# Altimeter.net
KiCad netlist of a schematic drawn in EAGLE
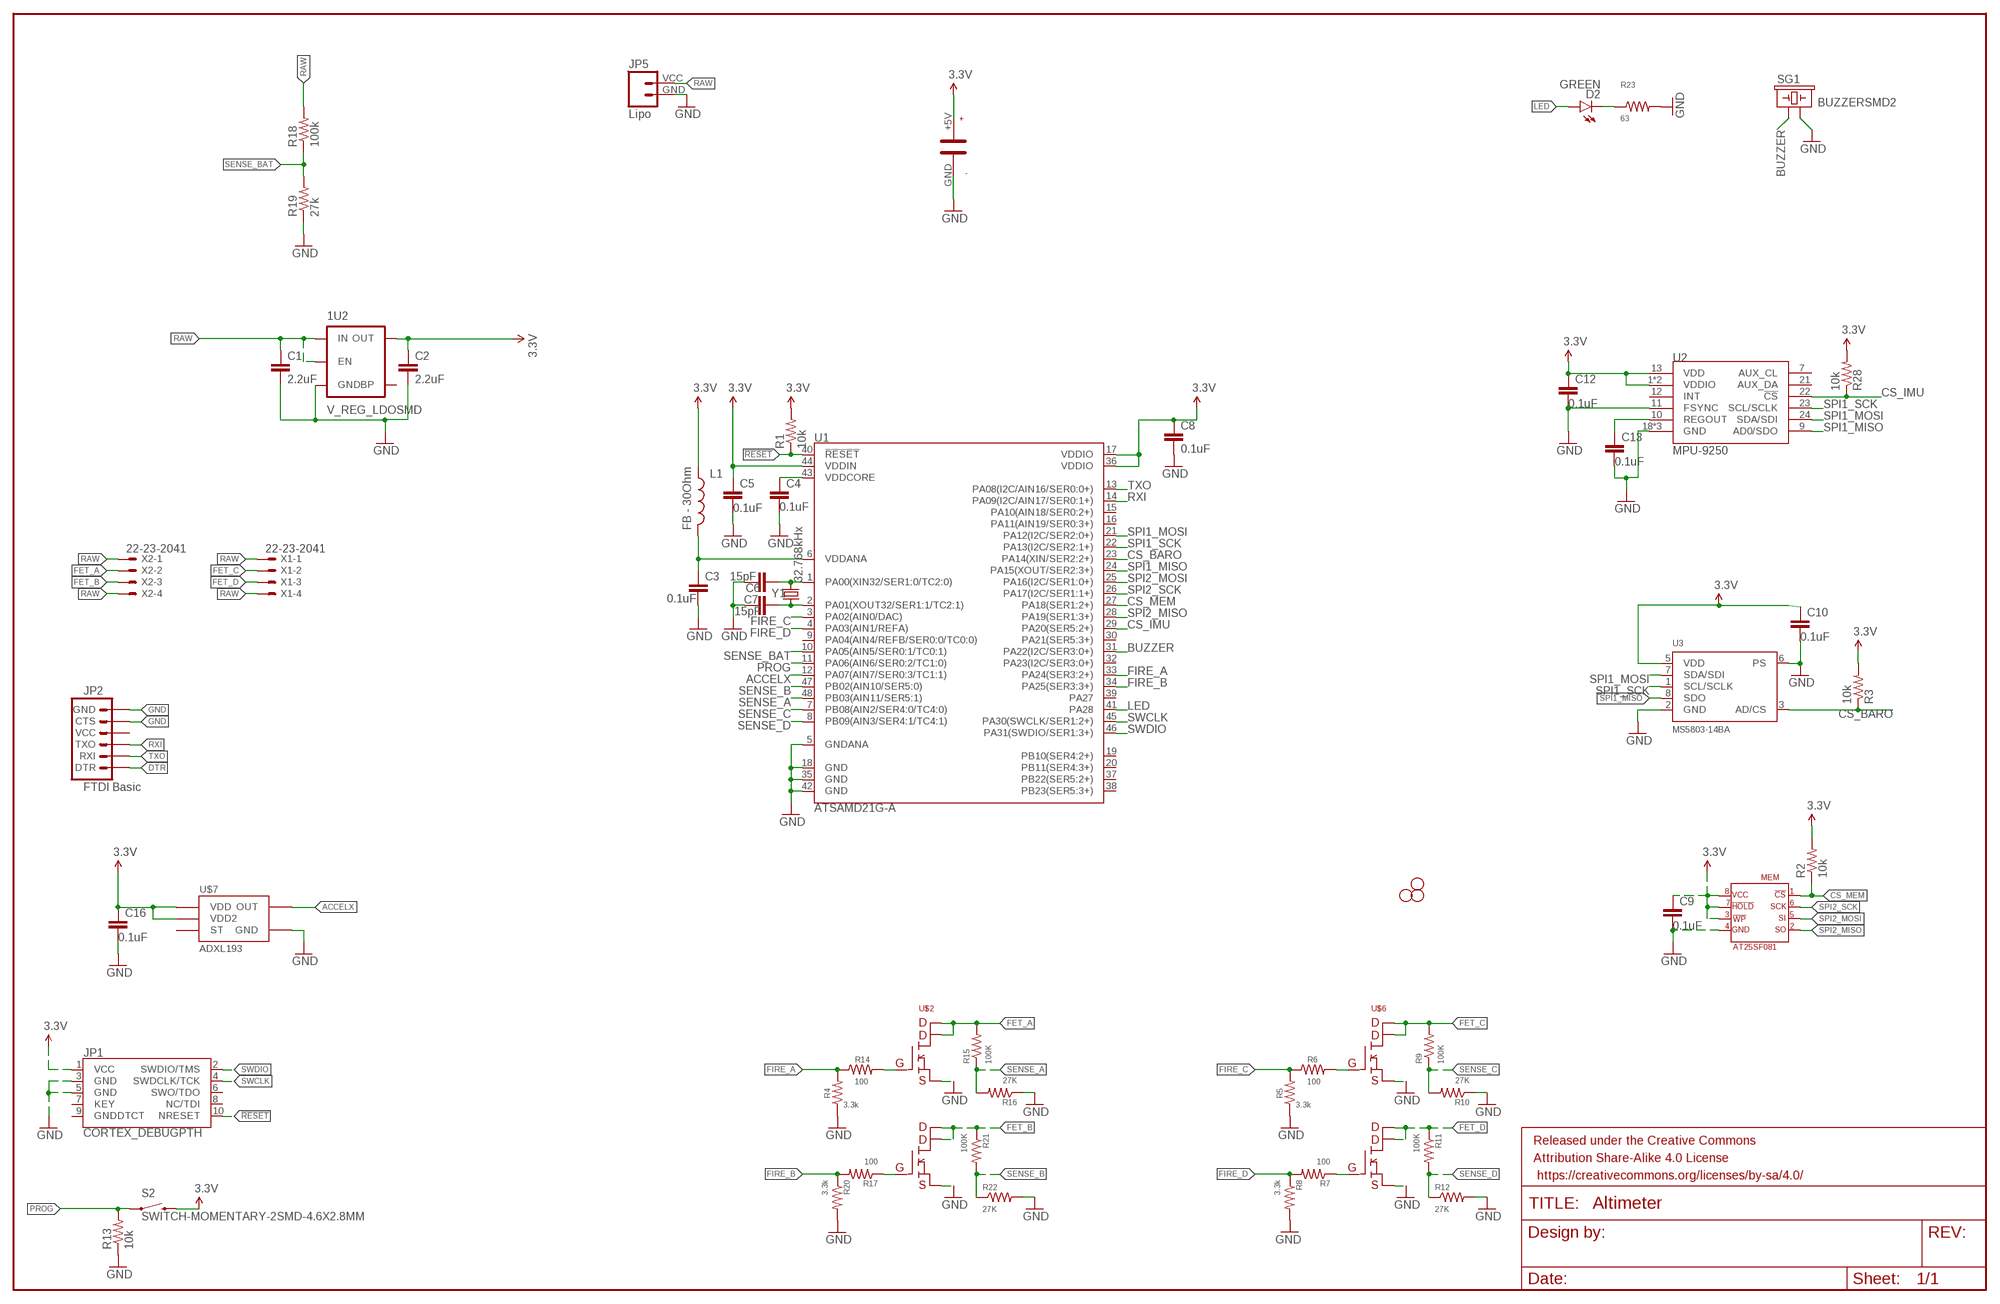
[diagram p0: schematic, sheet 1]

(export (version "E")
  (design (tool "Eeschema 10.0.6"))
  (components
    (comp (ref "1U2")
      (value "V_REG_LDOSMD")
      (footprint "eagle-import:SOT23-5")
      (libsource (lib "eagle-import") (part "V_REG_LDOSMD"))
    )
    (comp (ref "C1")
      (value "2.2uF")
      (footprint "eagle-import:0603-CAP")
      (libsource (lib "eagle-import") (part "CAP0603-CAP"))
    )
    (comp (ref "C2")
      (value "2.2uF")
      (footprint "eagle-import:0603-CAP")
      (libsource (lib "eagle-import") (part "CAP0603-CAP"))
    )
    (comp (ref "C3")
      (value "0.1uF")
      (footprint "eagle-import:0402-CAP")
      (libsource (lib "eagle-import") (part "SparkFun-Passives_CAP0402-CAP"))
    )
    (comp (ref "C4")
      (value "0.1uF")
      (footprint "eagle-import:0402-CAP")
      (libsource (lib "eagle-import") (part "SparkFun-Passives_CAP0402-CAP"))
    )
    (comp (ref "C5")
      (value "0.1uF")
      (footprint "eagle-import:0402-CAP")
      (libsource (lib "eagle-import") (part "SparkFun-Passives_CAP0402-CAP"))
    )
    (comp (ref "C6")
      (value "15pF")
      (footprint "eagle-import:0402-CAP")
      (libsource (lib "eagle-import") (part "SparkFun-Passives_CAP0402-CAP"))
    )
    (comp (ref "C7")
      (value "15pF")
      (footprint "eagle-import:0402-CAP")
      (libsource (lib "eagle-import") (part "SparkFun-Passives_CAP0402-CAP"))
    )
    (comp (ref "C8")
      (value "0.1uF")
      (footprint "eagle-import:0402-CAP")
      (libsource (lib "eagle-import") (part "SparkFun-Passives_CAP0402-CAP"))
    )
    (comp (ref "C9")
      (value "0.1uF")
      (footprint "eagle-import:0402-CAP")
      (libsource (lib "eagle-import") (part "SparkFun-Passives_CAP0402-CAP"))
    )
    (comp (ref "C10")
      (value "0.1uF")
      (footprint "eagle-import:0402-CAP")
      (libsource (lib "eagle-import") (part "SparkFun-Passives_CAP0402-CAP"))
    )
    (comp (ref "C12")
      (value "0.1uF")
      (footprint "eagle-import:0402-CAP")
      (libsource (lib "eagle-import") (part "SparkFun-Passives_CAP0402-CAP"))
    )
    (comp (ref "C13")
      (value "0.1uF")
      (footprint "eagle-import:0402-CAP")
      (libsource (lib "eagle-import") (part "SparkFun-Passives_CAP0402-CAP"))
    )
    (comp (ref "C16")
      (value "0.1uF")
      (footprint "eagle-import:0402-CAP")
      (libsource (lib "eagle-import") (part "SparkFun-Passives_CAP0402-CAP"))
    )
    (comp (ref "D2")
      (value "GREEN")
      (footprint "eagle-import:LED-1206")
      (libsource (lib "eagle-import") (part "LED-GREEN1206"))
    )
    (comp (ref "FRAME1")
      (value "FRAME-LEDGER")
      (footprint "eagle-import:CREATIVE_COMMONS")
      (libsource (lib "eagle-import") (part "FRAME-LEDGER"))
    )
    (comp (ref "JP1")
      (value "CORTEX_DEBUGPTH")
      (footprint "eagle-import:2X5-PTH-1.27MM")
      (libsource (lib "eagle-import") (part "CORTEX_DEBUGPTH"))
    )
    (comp (ref "JP2")
      (value "FTDI Basic")
      (footprint "eagle-import:1X06")
      (libsource (lib "eagle-import") (part "ARDUINO_SERIAL_PROGRAMPTH"))
    )
    (comp (ref "JP5")
      (value "Lipo")
      (footprint "eagle-import:JST-2-SMD-VERT")
      (libsource (lib "eagle-import") (part "M024UCON-15767"))
    )
    (comp (ref "L1")
      (value "FB - 30Ohm")
      (footprint "eagle-import:0603")
      (libsource (lib "eagle-import") (part "INDUCTOR0603"))
    )
    (comp (ref "MEM")
      (value "AT25SF081")
      (footprint "eagle-import:AT25SF081")
      (libsource (lib "eagle-import") (part "AT25SF081"))
    )
    (comp (ref "R1")
      (value "10k")
      (footprint "eagle-import:0402-RES")
      (libsource (lib "eagle-import") (part "RESISTOR0402-RES"))
    )
    (comp (ref "R2")
      (value "10k")
      (footprint "eagle-import:0402-RES")
      (libsource (lib "eagle-import") (part "RESISTOR0402-RES"))
    )
    (comp (ref "R3")
      (value "10k")
      (footprint "eagle-import:0402-RES")
      (libsource (lib "eagle-import") (part "RESISTOR0402-RES"))
    )
    (comp (ref "R4")
      (value "3.3k")
      (footprint "eagle-import:0402-RES")
      (libsource (lib "eagle-import") (part "RESISTOR0402"))
    )
    (comp (ref "R5")
      (value "3.3k")
      (footprint "eagle-import:0402-RES")
      (libsource (lib "eagle-import") (part "RESISTOR0402"))
    )
    (comp (ref "R6")
      (value "100")
      (footprint "eagle-import:0402-RES")
      (libsource (lib "eagle-import") (part "RESISTOR0402"))
    )
    (comp (ref "R7")
      (value "100")
      (footprint "eagle-import:0402-RES")
      (libsource (lib "eagle-import") (part "RESISTOR0402"))
    )
    (comp (ref "R8")
      (value "3.3k")
      (footprint "eagle-import:0402-RES")
      (libsource (lib "eagle-import") (part "RESISTOR0402"))
    )
    (comp (ref "R9")
      (value "100K")
      (footprint "eagle-import:0402-RES")
      (libsource (lib "eagle-import") (part "RESISTOR0402"))
    )
    (comp (ref "R10")
      (value "27K")
      (footprint "eagle-import:0402-RES")
      (libsource (lib "eagle-import") (part "RESISTOR0402"))
    )
    (comp (ref "R11")
      (value "100K")
      (footprint "eagle-import:0402-RES")
      (libsource (lib "eagle-import") (part "RESISTOR0402"))
    )
    (comp (ref "R12")
      (value "27K")
      (footprint "eagle-import:0402-RES")
      (libsource (lib "eagle-import") (part "RESISTOR0402"))
    )
    (comp (ref "R13")
      (value "10k")
      (footprint "eagle-import:0402-RES")
      (libsource (lib "eagle-import") (part "RESISTOR0402-RES"))
    )
    (comp (ref "R14")
      (value "100")
      (footprint "eagle-import:0402-RES")
      (libsource (lib "eagle-import") (part "RESISTOR0402"))
    )
    (comp (ref "R15")
      (value "100K")
      (footprint "eagle-import:0402-RES")
      (libsource (lib "eagle-import") (part "RESISTOR0402"))
    )
    (comp (ref "R16")
      (value "27K")
      (footprint "eagle-import:0402-RES")
      (libsource (lib "eagle-import") (part "RESISTOR0402"))
    )
    (comp (ref "R17")
      (value "100")
      (footprint "eagle-import:0402-RES")
      (libsource (lib "eagle-import") (part "RESISTOR0402"))
    )
    (comp (ref "R18")
      (value "100k")
      (footprint "eagle-import:0402-RES")
      (libsource (lib "eagle-import") (part "RESISTOR0402-RES"))
    )
    (comp (ref "R19")
      (value "27k")
      (footprint "eagle-import:0402-RES")
      (libsource (lib "eagle-import") (part "RESISTOR0402-RES"))
    )
    (comp (ref "R20")
      (value "3.3k")
      (footprint "eagle-import:0402-RES")
      (libsource (lib "eagle-import") (part "RESISTOR0402"))
    )
    (comp (ref "R21")
      (value "100K")
      (footprint "eagle-import:0402-RES")
      (libsource (lib "eagle-import") (part "RESISTOR0402"))
    )
    (comp (ref "R22")
      (value "27K")
      (footprint "eagle-import:0402-RES")
      (libsource (lib "eagle-import") (part "RESISTOR0402"))
    )
    (comp (ref "R23")
      (value "63")
      (footprint "eagle-import:0402-RES")
      (libsource (lib "eagle-import") (part "RESISTOR0402"))
    )
    (comp (ref "R28")
      (value "10k")
      (footprint "eagle-import:0402-RES")
      (libsource (lib "eagle-import") (part "RESISTOR0402-RES"))
    )
    (comp (ref "S2")
      (value "SWITCH-MOMENTARY-2SMD-4.6X2.8MM")
      (footprint "eagle-import:TACTILE_SWITCH_SMD_4.6X2.8MM")
      (libsource (lib "eagle-import") (part "SWITCH-MOMENTARY-2SMD-4.6X2.8MM"))
    )
    (comp (ref "SG1")
      (value "BUZZERSMD2")
      (footprint "eagle-import:BUZZER-CCV")
      (libsource (lib "eagle-import") (part "BUZZERSMD2"))
    )
    (comp (ref "STANDOFF2")
      (value "STAND-OFF")
      (footprint "eagle-import:STAND-OFF")
      (libsource (lib "eagle-import") (part "STAND-OFF"))
    )
    (comp (ref "STANDOFF3")
      (value "STAND-OFF")
      (footprint "eagle-import:STAND-OFF")
      (libsource (lib "eagle-import") (part "STAND-OFF"))
    )
    (comp (ref "STANDOFF4")
      (value "STAND-OFF")
      (footprint "eagle-import:STAND-OFF")
      (libsource (lib "eagle-import") (part "STAND-OFF"))
    )
    (comp (ref "U$1")
      (value "PB-5R0H104-R")
      (footprint "eagle-import:PB-5R0H104-R")
      (libsource (lib "eagle-import") (part "PB-5R0H104-R"))
    )
    (comp (ref "U$2")
      (value "SI7232DN")
      (footprint "eagle-import:SI7232DN")
      (libsource (lib "eagle-import") (part "SI7232DN"))
    )
    (comp (ref "U$6")
      (value "SI7232DN")
      (footprint "eagle-import:SI7232DN")
      (libsource (lib "eagle-import") (part "SI7232DN"))
    )
    (comp (ref "U$7")
      (value "ADXL193")
      (footprint "eagle-import:ADXL193")
      (libsource (lib "eagle-import") (part "ADXL193"))
    )
    (comp (ref "U1")
      (value "ATSAMD21G-A")
      (footprint "eagle-import:TQFP-48")
      (libsource (lib "eagle-import") (part "ATSAMD21G-A"))
    )
    (comp (ref "U2")
      (value "MPU-9250")
      (footprint "eagle-import:QFN24_PAD")
      (libsource (lib "eagle-import") (part "MPU-9250"))
    )
    (comp (ref "U3")
      (value "MS5803-14BA")
      (footprint "eagle-import:MS5803")
      (libsource (lib "eagle-import") (part "MS5803-14BA"))
    )
    (comp (ref "X1")
      (value "22-23-2041")
      (footprint "eagle-import:22-23-2041")
      (fields (field (name "MF") "MOLEX"))
      (libsource (lib "eagle-import") (part "22-23-2041"))
    )
    (comp (ref "X2")
      (value "22-23-2041")
      (footprint "eagle-import:22-23-2041")
      (fields (field (name "MF") "MOLEX"))
      (libsource (lib "eagle-import") (part "22-23-2041"))
    )
    (comp (ref "Y1")
      (value "32.768kHx")
      (footprint "eagle-import:CRYSTAL-SMD-3.2X1.5MM")
      (libsource (lib "eagle-import") (part "CRYSTAL3.2X1.5MM"))
    )
  )
  (nets
    (net (code "1") (name "/BUZZER") (class "Default")
      (node (ref "SG1") (pin "+") (pinfunction "1_+") (pintype "passive"))
      (node (ref "U1") (pin "31") (pinfunction "PA22(I2C/SER3:0+)_31") (pintype "bidirectional"))
    )
    (net (code "2") (name "/CS_BARO") (class "Default")
      (node (ref "R3") (pin "1") (pinfunction "1_1") (pintype "passive"))
      (node (ref "U1") (pin "23") (pinfunction "PA14(XIN/SER2:2+)_23") (pintype "bidirectional"))
      (node (ref "U3") (pin "3") (pinfunction "AD/CS_3") (pintype "bidirectional"))
    )
    (net (code "3") (name "/CS_IMU") (class "Default")
      (node (ref "R28") (pin "1") (pinfunction "1_1") (pintype "passive"))
      (node (ref "U1") (pin "29") (pinfunction "PA20(SER5:2+)_29") (pintype "bidirectional"))
      (node (ref "U2") (pin "22") (pinfunction "~{CS}_22") (pintype "bidirectional"))
    )
    (net (code "4") (name "/SPI1_MOSI") (class "Default")
      (node (ref "U1") (pin "21") (pinfunction "PA12(I2C/SER2:0+)_21") (pintype "bidirectional"))
      (node (ref "U2") (pin "24") (pinfunction "SDA/SDI_24") (pintype "bidirectional"))
      (node (ref "U3") (pin "7") (pinfunction "SDA/SDI_7") (pintype "bidirectional"))
    )
    (net (code "5") (name "/SPI1_SCK") (class "Default")
      (node (ref "U1") (pin "22") (pinfunction "PA13(I2C/SER2:1+)_22") (pintype "bidirectional"))
      (node (ref "U2") (pin "23") (pinfunction "SCL/SCLK_23") (pintype "bidirectional"))
      (node (ref "U3") (pin "1") (pinfunction "SCL/SCLK_1") (pintype "bidirectional"))
    )
    (net (code "6") (name "/~{RESET}") (class "Default")
      (node (ref "JP1") (pin "10") (pinfunction "NRESET_10") (pintype "bidirectional"))
      (node (ref "R1") (pin "1") (pinfunction "1_1") (pintype "passive"))
      (node (ref "U1") (pin "40") (pinfunction "~{RESET}_40") (pintype "bidirectional"))
    )
    (net (code "7") (name "3.3V") (class "Default")
      (node (ref "1U2") (pin "5") (pinfunction "OUT_5") (pintype "passive"))
      (node (ref "C10") (pin "1") (pinfunction "1_1") (pintype "passive"))
      (node (ref "C12") (pin "1") (pinfunction "1_1") (pintype "passive"))
      (node (ref "C16") (pin "1") (pinfunction "1_1") (pintype "passive"))
      (node (ref "C2") (pin "1") (pinfunction "1_1") (pintype "passive"))
      (node (ref "C5") (pin "1") (pinfunction "1_1") (pintype "passive"))
      (node (ref "C8") (pin "1") (pinfunction "1_1") (pintype "passive"))
      (node (ref "C9") (pin "1") (pinfunction "1_1") (pintype "passive"))
      (node (ref "JP1") (pin "1") (pinfunction "VCC_1") (pintype "bidirectional"))
      (node (ref "L1") (pin "1") (pinfunction "1_1") (pintype "passive"))
      (node (ref "MEM") (pin "!HOLD") (pinfunction "~{HOLD}_!HOLD") (pintype "bidirectional"))
      (node (ref "MEM") (pin "!WP") (pinfunction "~{WP}_!WP") (pintype "bidirectional"))
      (node (ref "MEM") (pin "VCC") (pinfunction "VCC_VCC") (pintype "bidirectional"))
      (node (ref "R1") (pin "2") (pinfunction "2_2") (pintype "passive"))
      (node (ref "R2") (pin "2") (pinfunction "2_2") (pintype "passive"))
      (node (ref "R28") (pin "2") (pinfunction "2_2") (pintype "passive"))
      (node (ref "R3") (pin "2") (pinfunction "2_2") (pintype "passive"))
      (node (ref "S2") (pin "3") (pinfunction "2_3") (pintype "passive"))
      (node (ref "S2") (pin "4") (pinfunction "2_4") (pintype "passive"))
      (node (ref "U$1") (pin "+5V") (pinfunction "+5V_+5V") (pintype "bidirectional"))
      (node (ref "U$7") (pin "P$7") (pinfunction "VDD_P$7") (pintype "bidirectional"))
      (node (ref "U$7") (pin "P$8") (pinfunction "VDD2_P$8") (pintype "bidirectional"))
      (node (ref "U1") (pin "17") (pinfunction "VDDIO_17") (pintype "bidirectional"))
      (node (ref "U1") (pin "36") (pinfunction "VDDIO_36") (pintype "bidirectional"))
      (node (ref "U1") (pin "44") (pinfunction "VDDIN_44") (pintype "bidirectional"))
      (node (ref "U2") (pin "1") (pinfunction "VDDIO_1") (pintype "bidirectional"))
      (node (ref "U2") (pin "13") (pinfunction "VDD_13") (pintype "bidirectional"))
      (node (ref "U2") (pin "8") (pinfunction "VDDIO_8") (pintype "bidirectional"))
      (node (ref "U3") (pin "5") (pinfunction "VDD_5") (pintype "bidirectional"))
    )
    (net (code "8") (name "ACCELX") (class "Default")
      (node (ref "U$7") (pin "P$6") (pinfunction "OUT_P$6") (pintype "bidirectional"))
      (node (ref "U1") (pin "12") (pinfunction "PA07(AIN7/SER0:3/TC1:1)_12") (pintype "bidirectional"))
    )
    (net (code "9") (name "CS_MEM") (class "Default")
      (node (ref "MEM") (pin "!CS") (pinfunction "~{CS}_!CS") (pintype "bidirectional"))
      (node (ref "R2") (pin "1") (pinfunction "1_1") (pintype "passive"))
      (node (ref "U1") (pin "27") (pinfunction "PA18(SER1:2+)_27") (pintype "bidirectional"))
    )
    (net (code "10") (name "DTR") (class "Default")
      (node (ref "JP2") (pin "1") (pinfunction "DTR_1") (pintype "passive"))
    )
    (net (code "11") (name "FET_A") (class "Default")
      (node (ref "R15") (pin "2") (pinfunction "2_2") (pintype "passive"))
      (node (ref "U$2") (pin "7") (pinfunction "PIN7_7") (pintype "bidirectional"))
      (node (ref "U$2") (pin "8") (pinfunction "PIN8_8") (pintype "bidirectional"))
      (node (ref "X2") (pin "2") (pinfunction "S_2") (pintype "passive"))
    )
    (net (code "12") (name "FET_B") (class "Default")
      (node (ref "R21") (pin "1") (pinfunction "1_1") (pintype "passive"))
      (node (ref "U$2") (pin "5") (pinfunction "PIN5_5") (pintype "bidirectional"))
      (node (ref "U$2") (pin "6") (pinfunction "PIN6_6") (pintype "bidirectional"))
      (node (ref "X2") (pin "3") (pinfunction "S_3") (pintype "passive"))
    )
    (net (code "13") (name "FET_C") (class "Default")
      (node (ref "R9") (pin "2") (pinfunction "2_2") (pintype "passive"))
      (node (ref "U$6") (pin "7") (pinfunction "PIN7_7") (pintype "bidirectional"))
      (node (ref "U$6") (pin "8") (pinfunction "PIN8_8") (pintype "bidirectional"))
      (node (ref "X1") (pin "2") (pinfunction "S_2") (pintype "passive"))
    )
    (net (code "14") (name "FET_D") (class "Default")
      (node (ref "R11") (pin "1") (pinfunction "1_1") (pintype "passive"))
      (node (ref "U$6") (pin "5") (pinfunction "PIN5_5") (pintype "bidirectional"))
      (node (ref "U$6") (pin "6") (pinfunction "PIN6_6") (pintype "bidirectional"))
      (node (ref "X1") (pin "3") (pinfunction "S_3") (pintype "passive"))
    )
    (net (code "15") (name "FIRE_A") (class "Default")
      (node (ref "R14") (pin "1") (pinfunction "1_1") (pintype "passive"))
      (node (ref "R4") (pin "2") (pinfunction "2_2") (pintype "passive"))
      (node (ref "U1") (pin "33") (pinfunction "PA24(SER3:2+)_33") (pintype "bidirectional"))
    )
    (net (code "16") (name "FIRE_B") (class "Default")
      (node (ref "R17") (pin "2") (pinfunction "2_2") (pintype "passive"))
      (node (ref "R20") (pin "1") (pinfunction "1_1") (pintype "passive"))
      (node (ref "U1") (pin "34") (pinfunction "PA25(SER3:3+)_34") (pintype "bidirectional"))
    )
    (net (code "17") (name "FIRE_C") (class "Default")
      (node (ref "R5") (pin "2") (pinfunction "2_2") (pintype "passive"))
      (node (ref "R6") (pin "1") (pinfunction "1_1") (pintype "passive"))
      (node (ref "U1") (pin "3") (pinfunction "PA02(AIN0/DAC)_3") (pintype "bidirectional"))
    )
    (net (code "18") (name "FIRE_D") (class "Default")
      (node (ref "R7") (pin "2") (pinfunction "2_2") (pintype "passive"))
      (node (ref "R8") (pin "1") (pinfunction "1_1") (pintype "passive"))
      (node (ref "U1") (pin "4") (pinfunction "PA03(AIN1/REFA)_4") (pintype "bidirectional"))
    )
    (net (code "19") (name "GND") (class "Default")
      (node (ref "1U2") (pin "2") (pinfunction "GND_2") (pintype "input"))
      (node (ref "C1") (pin "2") (pinfunction "2_2") (pintype "passive"))
      (node (ref "C10") (pin "2") (pinfunction "2_2") (pintype "passive"))
      (node (ref "C12") (pin "2") (pinfunction "2_2") (pintype "passive"))
      (node (ref "C13") (pin "2") (pinfunction "2_2") (pintype "passive"))
      (node (ref "C16") (pin "2") (pinfunction "2_2") (pintype "passive"))
      (node (ref "C2") (pin "2") (pinfunction "2_2") (pintype "passive"))
      (node (ref "C3") (pin "2") (pinfunction "2_2") (pintype "passive"))
      (node (ref "C4") (pin "2") (pinfunction "2_2") (pintype "passive"))
      (node (ref "C5") (pin "2") (pinfunction "2_2") (pintype "passive"))
      (node (ref "C6") (pin "2") (pinfunction "2_2") (pintype "passive"))
      (node (ref "C7") (pin "2") (pinfunction "2_2") (pintype "passive"))
      (node (ref "C8") (pin "2") (pinfunction "2_2") (pintype "passive"))
      (node (ref "C9") (pin "2") (pinfunction "2_2") (pintype "passive"))
      (node (ref "JP1") (pin "3") (pinfunction "GND_3") (pintype "bidirectional"))
      (node (ref "JP1") (pin "5") (pinfunction "GND_5") (pintype "bidirectional"))
      (node (ref "JP2") (pin "5") (pinfunction "CTS_5") (pintype "passive"))
      (node (ref "JP2") (pin "6") (pinfunction "GND_6") (pintype "passive"))
      (node (ref "JP5") (pin "GND") (pinfunction "1_GND") (pintype "passive"))
      (node (ref "MEM") (pin "GND") (pinfunction "GND_GND") (pintype "bidirectional"))
      (node (ref "R10") (pin "1") (pinfunction "1_1") (pintype "passive"))
      (node (ref "R12") (pin "2") (pinfunction "2_2") (pintype "passive"))
      (node (ref "R13") (pin "1") (pinfunction "1_1") (pintype "passive"))
      (node (ref "R16") (pin "1") (pinfunction "1_1") (pintype "passive"))
      (node (ref "R19") (pin "1") (pinfunction "1_1") (pintype "passive"))
      (node (ref "R20") (pin "2") (pinfunction "2_2") (pintype "passive"))
      (node (ref "R22") (pin "2") (pinfunction "2_2") (pintype "passive"))
      (node (ref "R23") (pin "2") (pinfunction "2_2") (pintype "passive"))
      (node (ref "R4") (pin "1") (pinfunction "1_1") (pintype "passive"))
      (node (ref "R5") (pin "1") (pinfunction "1_1") (pintype "passive"))
      (node (ref "R8") (pin "2") (pinfunction "2_2") (pintype "passive"))
      (node (ref "SG1") (pin "-") (pinfunction "2_-") (pintype "passive"))
      (node (ref "U$1") (pin "GND") (pinfunction "GND_GND") (pintype "bidirectional"))
      (node (ref "U$2") (pin "1") (pinfunction "PIN1_1") (pintype "bidirectional"))
      (node (ref "U$2") (pin "3") (pinfunction "PIN3_3") (pintype "bidirectional"))
      (node (ref "U$6") (pin "1") (pinfunction "PIN1_1") (pintype "bidirectional"))
      (node (ref "U$6") (pin "3") (pinfunction "PIN3_3") (pintype "bidirectional"))
      (node (ref "U$7") (pin "P$3") (pinfunction "GND_P$3") (pintype "bidirectional"))
      (node (ref "U1") (pin "18") (pinfunction "GND_18") (pintype "bidirectional"))
      (node (ref "U1") (pin "35") (pinfunction "GND_35") (pintype "bidirectional"))
      (node (ref "U1") (pin "42") (pinfunction "GND_42") (pintype "bidirectional"))
      (node (ref "U1") (pin "5") (pinfunction "GNDANA_5") (pintype "bidirectional"))
      (node (ref "U2") (pin "11") (pinfunction "FSYNC_11") (pintype "bidirectional"))
      (node (ref "U2") (pin "18") (pinfunction "GND_18") (pintype "bidirectional"))
      (node (ref "U2") (pin "20") (pinfunction "GND_20") (pintype "bidirectional"))
      (node (ref "U2") (pin "CENTER") (pinfunction "GND_CENTER") (pintype "bidirectional"))
      (node (ref "U3") (pin "2") (pinfunction "GND_2") (pintype "bidirectional"))
      (node (ref "U3") (pin "6") (pinfunction "PS_6") (pintype "bidirectional"))
    )
    (net (code "20") (name "LED") (class "Default")
      (node (ref "D2") (pin "A") (pinfunction "A_A") (pintype "passive"))
      (node (ref "U1") (pin "41") (pinfunction "PA28_41") (pintype "bidirectional"))
    )
    (net (code "21") (name "Net-(D2-PadC)") (class "Default")
      (node (ref "D2") (pin "C") (pinfunction "C_C") (pintype "passive"))
      (node (ref "R23") (pin "1") (pinfunction "1_1") (pintype "passive"))
    )
    (net (code "22") (name "Net-(U$2-PIN2)") (class "Default")
      (node (ref "R14") (pin "2") (pinfunction "2_2") (pintype "passive"))
      (node (ref "U$2") (pin "2") (pinfunction "PIN2_2") (pintype "bidirectional"))
    )
    (net (code "23") (name "Net-(U$2-PIN4)") (class "Default")
      (node (ref "R17") (pin "1") (pinfunction "1_1") (pintype "passive"))
      (node (ref "U$2") (pin "4") (pinfunction "PIN4_4") (pintype "bidirectional"))
    )
    (net (code "24") (name "Net-(U$6-PIN2)") (class "Default")
      (node (ref "R6") (pin "2") (pinfunction "2_2") (pintype "passive"))
      (node (ref "U$6") (pin "2") (pinfunction "PIN2_2") (pintype "bidirectional"))
    )
    (net (code "25") (name "Net-(U$6-PIN4)") (class "Default")
      (node (ref "R7") (pin "1") (pinfunction "1_1") (pintype "passive"))
      (node (ref "U$6") (pin "4") (pinfunction "PIN4_4") (pintype "bidirectional"))
    )
    (net (code "26") (name "Net-(U1-PA00(XIN32{slash}SER1:0{slash}TC2:0))") (class "Default")
      (node (ref "C6") (pin "1") (pinfunction "1_1") (pintype "passive"))
      (node (ref "U1") (pin "1") (pinfunction "PA00(XIN32/SER1:0/TC2:0)_1") (pintype "bidirectional"))
      (node (ref "Y1") (pin "P$2") (pinfunction "2_P$2") (pintype "passive"))
    )
    (net (code "27") (name "Net-(U1-PA01(XOUT32{slash}SER1:1{slash}TC2:1))") (class "Default")
      (node (ref "C7") (pin "1") (pinfunction "1_1") (pintype "passive"))
      (node (ref "U1") (pin "2") (pinfunction "PA01(XOUT32/SER1:1/TC2:1)_2") (pintype "bidirectional"))
      (node (ref "Y1") (pin "P$1") (pinfunction "1_P$1") (pintype "passive"))
    )
    (net (code "28") (name "Net-(U1-VDDANA)") (class "Default")
      (node (ref "C3") (pin "1") (pinfunction "1_1") (pintype "passive"))
      (node (ref "L1") (pin "2") (pinfunction "2_2") (pintype "passive"))
      (node (ref "U1") (pin "6") (pinfunction "VDDANA_6") (pintype "bidirectional"))
    )
    (net (code "29") (name "Net-(U1-VDDCORE)") (class "Default")
      (node (ref "C4") (pin "1") (pinfunction "1_1") (pintype "passive"))
      (node (ref "U1") (pin "43") (pinfunction "VDDCORE_43") (pintype "bidirectional"))
    )
    (net (code "30") (name "Net-(U2-REGOUT)") (class "Default")
      (node (ref "C13") (pin "1") (pinfunction "1_1") (pintype "passive"))
      (node (ref "U2") (pin "10") (pinfunction "REGOUT_10") (pintype "bidirectional"))
    )
    (net (code "31") (name "PROG") (class "Default")
      (node (ref "R13") (pin "2") (pinfunction "2_2") (pintype "passive"))
      (node (ref "S2") (pin "1") (pinfunction "1_1") (pintype "passive"))
      (node (ref "S2") (pin "2") (pinfunction "1_2") (pintype "passive"))
      (node (ref "U1") (pin "11") (pinfunction "PA06(AIN6/SER0:2/TC1:0)_11") (pintype "bidirectional"))
    )
    (net (code "32") (name "RAW") (class "Default")
      (node (ref "1U2") (pin "1") (pinfunction "IN_1") (pintype "input"))
      (node (ref "1U2") (pin "3") (pinfunction "EN_3") (pintype "input"))
      (node (ref "C1") (pin "1") (pinfunction "1_1") (pintype "passive"))
      (node (ref "JP5") (pin "VCC") (pinfunction "2_VCC") (pintype "passive"))
      (node (ref "R18") (pin "2") (pinfunction "2_2") (pintype "passive"))
      (node (ref "X1") (pin "1") (pinfunction "S_1") (pintype "passive"))
      (node (ref "X1") (pin "4") (pinfunction "S_4") (pintype "passive"))
      (node (ref "X2") (pin "1") (pinfunction "S_1") (pintype "passive"))
      (node (ref "X2") (pin "4") (pinfunction "S_4") (pintype "passive"))
    )
    (net (code "33") (name "RXI") (class "Default")
      (node (ref "JP2") (pin "3") (pinfunction "TXO_3") (pintype "passive"))
      (node (ref "U1") (pin "14") (pinfunction "PA09(I2C/AIN17/SER0:1+)_14") (pintype "bidirectional"))
    )
    (net (code "34") (name "SENSE_A") (class "Default")
      (node (ref "R15") (pin "1") (pinfunction "1_1") (pintype "passive"))
      (node (ref "R16") (pin "2") (pinfunction "2_2") (pintype "passive"))
      (node (ref "U1") (pin "48") (pinfunction "PB03(AIN11/SER5:1)_48") (pintype "bidirectional"))
    )
    (net (code "35") (name "SENSE_B") (class "Default")
      (node (ref "R21") (pin "2") (pinfunction "2_2") (pintype "passive"))
      (node (ref "R22") (pin "1") (pinfunction "1_1") (pintype "passive"))
      (node (ref "U1") (pin "47") (pinfunction "PB02(AIN10/SER5:0)_47") (pintype "bidirectional"))
    )
    (net (code "36") (name "SENSE_BAT") (class "Default")
      (node (ref "R18") (pin "1") (pinfunction "1_1") (pintype "passive"))
      (node (ref "R19") (pin "2") (pinfunction "2_2") (pintype "passive"))
      (node (ref "U1") (pin "10") (pinfunction "PA05(AIN5/SER0:1/TC0:1)_10") (pintype "bidirectional"))
    )
    (net (code "37") (name "SENSE_C") (class "Default")
      (node (ref "R10") (pin "2") (pinfunction "2_2") (pintype "passive"))
      (node (ref "R9") (pin "1") (pinfunction "1_1") (pintype "passive"))
      (node (ref "U1") (pin "7") (pinfunction "PB08(AIN2/SER4:0/TC4:0)_7") (pintype "bidirectional"))
    )
    (net (code "38") (name "SENSE_D") (class "Default")
      (node (ref "R11") (pin "2") (pinfunction "2_2") (pintype "passive"))
      (node (ref "R12") (pin "1") (pinfunction "1_1") (pintype "passive"))
      (node (ref "U1") (pin "8") (pinfunction "PB09(AIN3/SER4:1/TC4:1)_8") (pintype "bidirectional"))
    )
    (net (code "39") (name "SPI1_MISO") (class "Default")
      (node (ref "U1") (pin "24") (pinfunction "PA15(XOUT/SER2:3+)_24") (pintype "bidirectional"))
      (node (ref "U2") (pin "9") (pinfunction "AD0/SDO_9") (pintype "bidirectional"))
      (node (ref "U3") (pin "8") (pinfunction "SDO_8") (pintype "bidirectional"))
    )
    (net (code "40") (name "SPI2_MISO") (class "Default")
      (node (ref "MEM") (pin "SO") (pinfunction "SO_SO") (pintype "bidirectional"))
      (node (ref "U1") (pin "28") (pinfunction "PA19(SER1:3+)_28") (pintype "bidirectional"))
    )
    (net (code "41") (name "SPI2_MOSI") (class "Default")
      (node (ref "MEM") (pin "SI") (pinfunction "SI_SI") (pintype "bidirectional"))
      (node (ref "U1") (pin "25") (pinfunction "PA16(I2C/SER1:0+)_25") (pintype "bidirectional"))
    )
    (net (code "42") (name "SPI2_SCK") (class "Default")
      (node (ref "MEM") (pin "SCK") (pinfunction "SCK_SCK") (pintype "bidirectional"))
      (node (ref "U1") (pin "26") (pinfunction "PA17(I2C/SER1:1+)_26") (pintype "bidirectional"))
    )
    (net (code "43") (name "SWCLK") (class "Default")
      (node (ref "JP1") (pin "4") (pinfunction "SWDCLK/TCK_4") (pintype "bidirectional"))
      (node (ref "U1") (pin "45") (pinfunction "PA30(SWCLK/SER1:2+)_45") (pintype "bidirectional"))
    )
    (net (code "44") (name "SWDIO") (class "Default")
      (node (ref "JP1") (pin "2") (pinfunction "SWDIO/TMS_2") (pintype "bidirectional"))
      (node (ref "U1") (pin "46") (pinfunction "PA31(SWDIO/SER1:3+)_46") (pintype "bidirectional"))
    )
    (net (code "45") (name "TXO") (class "Default")
      (node (ref "JP2") (pin "2") (pinfunction "RXI_2") (pintype "passive"))
      (node (ref "U1") (pin "13") (pinfunction "PA08(I2C/AIN16/SER0:0+)_13") (pintype "bidirectional"))
    )
    (net (code "46") (name "unconnected-(1U2-BP-Pad4)") (class "Default")
      (node (ref "1U2") (pin "4") (pinfunction "BP_4") (pintype "input"))
    )
    (net (code "47") (name "unconnected-(JP1-GNDDTCT-Pad9)") (class "Default")
      (node (ref "JP1") (pin "9") (pinfunction "GNDDTCT_9") (pintype "bidirectional"))
    )
    (net (code "48") (name "unconnected-(JP1-KEY-Pad7)") (class "Default")
      (node (ref "JP1") (pin "7") (pinfunction "KEY_7") (pintype "bidirectional"))
    )
    (net (code "49") (name "unconnected-(JP1-NC{slash}TDI-Pad8)") (class "Default")
      (node (ref "JP1") (pin "8") (pinfunction "NC/TDI_8") (pintype "bidirectional"))
    )
    (net (code "50") (name "unconnected-(JP1-SWO{slash}TDO-Pad6)") (class "Default")
      (node (ref "JP1") (pin "6") (pinfunction "SWO/TDO_6") (pintype "bidirectional"))
    )
    (net (code "51") (name "unconnected-(JP2-VCC-Pad4)") (class "Default")
      (node (ref "JP2") (pin "4") (pinfunction "VCC_4") (pintype "passive"))
    )
    (net (code "52") (name "unconnected-(U$7-ST-PadP$4)") (class "Default")
      (node (ref "U$7") (pin "P$4") (pinfunction "ST_P$4") (pintype "bidirectional"))
    )
    (net (code "53") (name "unconnected-(U1-PA04(AIN4{slash}REFB{slash}SER0:0{slash}TC0:0)-Pad9)") (class "Default")
      (node (ref "U1") (pin "9") (pinfunction "PA04(AIN4/REFB/SER0:0/TC0:0)_9") (pintype "bidirectional"))
    )
    (net (code "54") (name "unconnected-(U1-PA10(AIN18{slash}SER0:2+)-Pad15)") (class "Default")
      (node (ref "U1") (pin "15") (pinfunction "PA10(AIN18/SER0:2+)_15") (pintype "bidirectional"))
    )
    (net (code "55") (name "unconnected-(U1-PA11(AIN19{slash}SER0:3+)-Pad16)") (class "Default")
      (node (ref "U1") (pin "16") (pinfunction "PA11(AIN19/SER0:3+)_16") (pintype "bidirectional"))
    )
    (net (code "56") (name "unconnected-(U1-PA21(SER5:3+)-Pad30)") (class "Default")
      (node (ref "U1") (pin "30") (pinfunction "PA21(SER5:3+)_30") (pintype "bidirectional"))
    )
    (net (code "57") (name "unconnected-(U1-PA23(I2C{slash}SER3:0+)-Pad32)") (class "Default")
      (node (ref "U1") (pin "32") (pinfunction "PA23(I2C/SER3:0+)_32") (pintype "bidirectional"))
    )
    (net (code "58") (name "unconnected-(U1-PA27-Pad39)") (class "Default")
      (node (ref "U1") (pin "39") (pinfunction "PA27_39") (pintype "bidirectional"))
    )
    (net (code "59") (name "unconnected-(U1-PB10(SER4:2+)-Pad19)") (class "Default")
      (node (ref "U1") (pin "19") (pinfunction "PB10(SER4:2+)_19") (pintype "bidirectional"))
    )
    (net (code "60") (name "unconnected-(U1-PB11(SER4:3+)-Pad20)") (class "Default")
      (node (ref "U1") (pin "20") (pinfunction "PB11(SER4:3+)_20") (pintype "bidirectional"))
    )
    (net (code "61") (name "unconnected-(U1-PB22(SER5:2+)-Pad37)") (class "Default")
      (node (ref "U1") (pin "37") (pinfunction "PB22(SER5:2+)_37") (pintype "bidirectional"))
    )
    (net (code "62") (name "unconnected-(U1-PB23(SER5:3+)-Pad38)") (class "Default")
      (node (ref "U1") (pin "38") (pinfunction "PB23(SER5:3+)_38") (pintype "bidirectional"))
    )
    (net (code "63") (name "unconnected-(U2-AUX_CL-Pad7)") (class "Default")
      (node (ref "U2") (pin "7") (pinfunction "AUX_CL_7") (pintype "bidirectional"))
    )
    (net (code "64") (name "unconnected-(U2-AUX_DA-Pad21)") (class "Default")
      (node (ref "U2") (pin "21") (pinfunction "AUX_DA_21") (pintype "bidirectional"))
    )
    (net (code "65") (name "unconnected-(U2-INT-Pad12)") (class "Default")
      (node (ref "U2") (pin "12") (pinfunction "INT_12") (pintype "bidirectional"))
    )
  )
)
